# 1_Root.net
KiCad netlist of a schematic drawn in Altium Designer
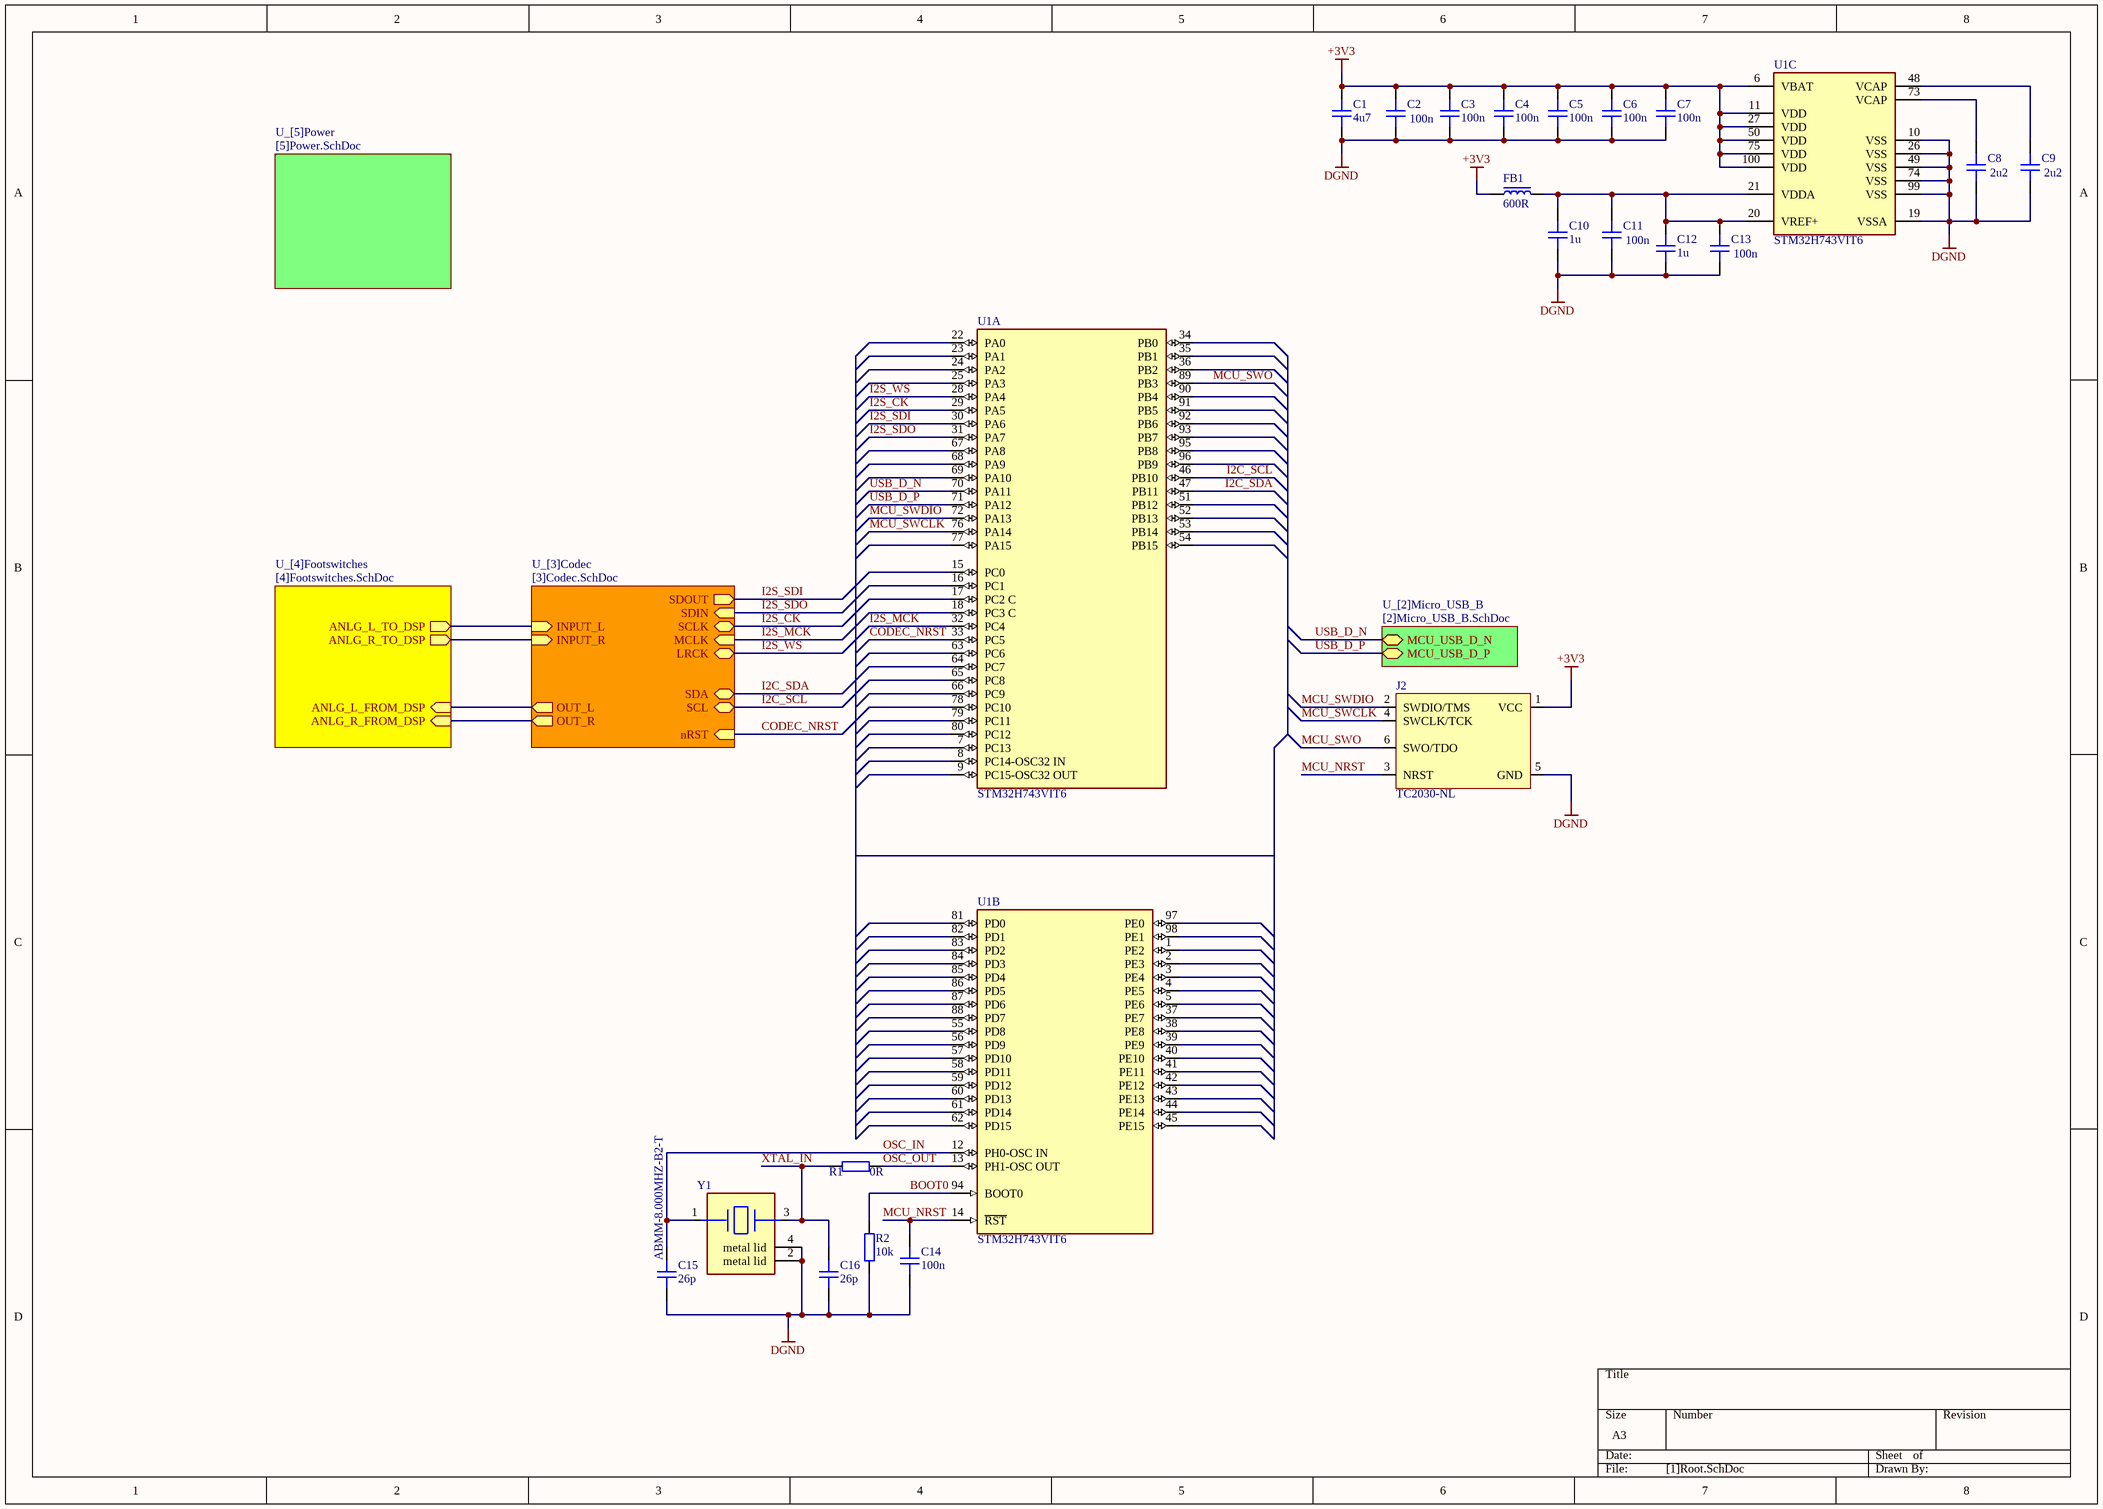
[diagram p0: [1]Root.SchDoc]

(export (version "E")
  (design (tool "Eeschema 10.0.6"))
  (components
    (comp (ref "C1")
      (value "4u7")
      (footprint "CAP_0603")
      (description "16V")
      (libsource (lib "Schematic-Lib-PhilsLab") (part "CAP_0603"))
    )
    (comp (ref "C2")
      (value "100n")
      (footprint "CAP_0402")
      (description "16V")
      (libsource (lib "Schematic-Lib-PhilsLab") (part "CAP_0402"))
    )
    (comp (ref "C3")
      (value "100n")
      (footprint "CAP_0402")
      (description "16V")
      (libsource (lib "Schematic-Lib-PhilsLab") (part "CAP_0402"))
    )
    (comp (ref "C4")
      (value "100n")
      (footprint "CAP_0402")
      (description "16V")
      (libsource (lib "Schematic-Lib-PhilsLab") (part "CAP_0402"))
    )
    (comp (ref "C5")
      (value "100n")
      (footprint "CAP_0402")
      (description "16V")
      (libsource (lib "Schematic-Lib-PhilsLab") (part "CAP_0402"))
    )
    (comp (ref "C6")
      (value "100n")
      (footprint "CAP_0402")
      (description "16V")
      (libsource (lib "Schematic-Lib-PhilsLab") (part "CAP_0402"))
    )
    (comp (ref "C7")
      (value "100n")
      (footprint "CAP_0402")
      (description "16V")
      (libsource (lib "Schematic-Lib-PhilsLab") (part "CAP_0402"))
    )
    (comp (ref "C8")
      (value "2u2")
      (footprint "CAP_0402")
      (description "16V")
      (libsource (lib "Schematic-Lib-PhilsLab") (part "CAP_0402"))
    )
    (comp (ref "C9")
      (value "2u2")
      (footprint "CAP_0402")
      (description "16V")
      (libsource (lib "Schematic-Lib-PhilsLab") (part "CAP_0402"))
    )
    (comp (ref "C10")
      (value "1u")
      (footprint "CAP_0603")
      (description "16V")
      (libsource (lib "Schematic-Lib-PhilsLab") (part "CAP_0603"))
    )
    (comp (ref "C11")
      (value "100n")
      (footprint "CAP_0402")
      (description "16V")
      (libsource (lib "Schematic-Lib-PhilsLab") (part "CAP_0402"))
    )
    (comp (ref "C12")
      (value "1u")
      (footprint "CAP_0603")
      (description "16V")
      (libsource (lib "Schematic-Lib-PhilsLab") (part "CAP_0603"))
    )
    (comp (ref "C13")
      (value "100n")
      (footprint "CAP_0402")
      (description "16V")
      (libsource (lib "Schematic-Lib-PhilsLab") (part "CAP_0402"))
    )
    (comp (ref "C14")
      (value "100n")
      (footprint "CAP_0402")
      (description "16V")
      (libsource (lib "Schematic-Lib-PhilsLab") (part "CAP_0402"))
    )
    (comp (ref "C15")
      (value "26p")
      (footprint "CAP_0402")
      (description "Capacitor SMD 0402")
      (libsource (lib "Schematic-Lib-PhilsLab") (part "CAP_0402"))
    )
    (comp (ref "C16")
      (value "26p")
      (footprint "CAP_0402")
      (description "Capacitor SMD 0402")
      (libsource (lib "Schematic-Lib-PhilsLab") (part "CAP_0402"))
    )
    (comp (ref "FB1")
      (value "600R")
      (footprint "FB_0805")
      (description "300mOhm DC, 600R @ 100MHz")
      (libsource (lib "Schematic-Lib-PhilsLab") (part "FB_0805"))
    )
    (comp (ref "J2")
      (value "TC2030-NL")
      (footprint "TC2030-NL-FP")
      (description "Tag-Connect No-Solder SWD Debug Connector (No Legs) DO NOT PLACE")
      (fields
        (field (name "MANUFACTURER") "Tag-Connect")
        (field (name "MANUFACTURER PART NUMBER") "TC2030-NL-FP")
      )
      (libsource (lib "Schematic-Lib-PhilsLab") (part "TC2030-NL"))
    )
    (comp (ref "R1")
      (value "0R")
      (footprint "RES_0402")
      (description "Resistor SMD 0402")
      (libsource (lib "Schematic-Lib-PhilsLab") (part "RES_0402"))
    )
    (comp (ref "R2")
      (value "10k")
      (footprint "RES_0402")
      (description "Resistor SMD 0402")
      (libsource (lib "Schematic-Lib-PhilsLab") (part "RES_0402"))
    )
    (comp (ref "U1")
      (value "STM32H743VIT6")
      (footprint "FP-LQFP100-1L-MFG")
      (description "IC MCU 32BIT 2MB FLASH 100LQFP")
      (fields
        (field (name "OCTOPART") "https://octopart.com/stm32h743vit6-stmicroelectronics-76372527")
        (field (name "MANUFACTURER") "STMicroelectronics")
      )
      (libsource (lib "Altium Content Vault") (part "01082ce2885d1d16a22823c45526fe6"))
    )
    (comp (ref "Y1")
      (value "ABMM-8.000MHZ-B2-T")
      (footprint "FP-ABMM-MFG")
      (description "CRYSTAL 8.0000MHZ 18PF SMD")
      (fields (field (name "TOLERANCE") "20ppm"))
      (libsource (lib "Altium Content Vault") (part "0c2a4651d804c61cb55e58ae8c0fb54"))
    )
  )
  (nets
    (net (code "1") (name "+3V3") (class "Default")
      (node (ref "C1") (pin "2") (pinfunction "2_2") (pintype "passive"))
      (node (ref "C2") (pin "2") (pinfunction "2_2") (pintype "passive"))
      (node (ref "C3") (pin "2") (pinfunction "2_2") (pintype "passive"))
      (node (ref "C4") (pin "2") (pinfunction "2_2") (pintype "passive"))
      (node (ref "C5") (pin "2") (pinfunction "2_2") (pintype "passive"))
      (node (ref "C6") (pin "2") (pinfunction "2_2") (pintype "passive"))
      (node (ref "C7") (pin "2") (pinfunction "2_2") (pintype "passive"))
      (node (ref "FB1") (pin "1") (pinfunction "1_1") (pintype "passive"))
      (node (ref "J2") (pin "1") (pinfunction "VCC_1") (pintype "passive"))
      (node (ref "U1") (pin "100") (pinfunction "VDD_100") (pintype "power_in"))
      (node (ref "U1") (pin "11") (pinfunction "VDD_11") (pintype "power_in"))
      (node (ref "U1") (pin "27") (pinfunction "VDD_27") (pintype "power_in"))
      (node (ref "U1") (pin "50") (pinfunction "VDD_50") (pintype "power_in"))
      (node (ref "U1") (pin "6") (pinfunction "VBAT_6") (pintype "power_in"))
      (node (ref "U1") (pin "75") (pinfunction "VDD_75") (pintype "power_in"))
    )
    (net (code "4") (name "/BOOT0") (class "Default")
      (node (ref "R2") (pin "2") (pinfunction "2_2") (pintype "passive"))
      (node (ref "U1") (pin "94") (pinfunction "BOOT0_94") (pintype "input"))
    )
    (net (code "5") (name "/CODEC_NRST") (class "Default")
      (node (ref "U1") (pin "33") (pinfunction "PC5_33") (pintype "bidirectional"))
    )
    (net (code "6") (name "/I2C_SCL") (class "Default")
      (node (ref "U1") (pin "46") (pinfunction "PB10_46") (pintype "bidirectional"))
    )
    (net (code "7") (name "/I2C_SDA") (class "Default")
      (node (ref "U1") (pin "47") (pinfunction "PB11_47") (pintype "bidirectional"))
    )
    (net (code "8") (name "/I2S_CK") (class "Default")
      (node (ref "U1") (pin "29") (pinfunction "PA5_29") (pintype "bidirectional"))
    )
    (net (code "9") (name "/I2S_MCK") (class "Default")
      (node (ref "U1") (pin "32") (pinfunction "PC4_32") (pintype "bidirectional"))
    )
    (net (code "10") (name "/I2S_SDI") (class "Default")
      (node (ref "U1") (pin "30") (pinfunction "PA6_30") (pintype "bidirectional"))
    )
    (net (code "11") (name "/I2S_SDO") (class "Default")
      (node (ref "U1") (pin "31") (pinfunction "PA7_31") (pintype "bidirectional"))
    )
    (net (code "12") (name "/I2S_WS") (class "Default")
      (node (ref "U1") (pin "28") (pinfunction "PA4_28") (pintype "bidirectional"))
    )
    (net (code "13") (name "/MCU_NRST") (class "Default")
      (node (ref "C14") (pin "2") (pinfunction "2_2") (pintype "passive"))
      (node (ref "J2") (pin "3") (pinfunction "NRST_3") (pintype "passive"))
      (node (ref "U1") (pin "14") (pinfunction "~{RST}_14") (pintype "input"))
    )
    (net (code "14") (name "/MCU_SWCLK") (class "Default")
      (node (ref "J2") (pin "4") (pinfunction "SWCLK/TCK_4") (pintype "passive"))
      (node (ref "U1") (pin "76") (pinfunction "PA14_76") (pintype "bidirectional"))
    )
    (net (code "15") (name "/MCU_SWDIO") (class "Default")
      (node (ref "J2") (pin "2") (pinfunction "SWDIO/TMS_2") (pintype "passive"))
      (node (ref "U1") (pin "72") (pinfunction "PA13_72") (pintype "bidirectional"))
    )
    (net (code "16") (name "/MCU_SWO") (class "Default")
      (node (ref "J2") (pin "6") (pinfunction "SWO/TDO_6") (pintype "passive"))
      (node (ref "U1") (pin "89") (pinfunction "PB3_89") (pintype "bidirectional"))
    )
    (net (code "17") (name "/OSC_IN") (class "Default")
      (node (ref "C15") (pin "2") (pinfunction "2_2") (pintype "passive"))
      (node (ref "U1") (pin "12") (pinfunction "PH0-OSC_IN_12") (pintype "bidirectional"))
      (node (ref "Y1") (pin "1") (pinfunction "1_1") (pintype "passive"))
    )
    (net (code "18") (name "/OSC_OUT") (class "Default")
      (node (ref "R1") (pin "2") (pinfunction "2_2") (pintype "passive"))
      (node (ref "U1") (pin "13") (pinfunction "PH1-OSC_OUT_13") (pintype "bidirectional"))
    )
    (net (code "21") (name "/USB_D_N") (class "Default")
      (node (ref "U1") (pin "70") (pinfunction "PA11_70") (pintype "bidirectional"))
    )
    (net (code "22") (name "/USB_D_P") (class "Default")
      (node (ref "U1") (pin "71") (pinfunction "PA12_71") (pintype "bidirectional"))
    )
    (net (code "23") (name "/XTAL_IN") (class "Default")
      (node (ref "C16") (pin "2") (pinfunction "2_2") (pintype "passive"))
      (node (ref "R1") (pin "1") (pinfunction "1_1") (pintype "passive"))
      (node (ref "Y1") (pin "3") (pinfunction "3_3") (pintype "passive"))
    )
    (net (code "24") (name "DGND") (class "Default")
      (node (ref "C1") (pin "1") (pinfunction "1_1") (pintype "passive"))
      (node (ref "C10") (pin "1") (pinfunction "1_1") (pintype "passive"))
      (node (ref "C11") (pin "1") (pinfunction "1_1") (pintype "passive"))
      (node (ref "C12") (pin "1") (pinfunction "1_1") (pintype "passive"))
      (node (ref "C13") (pin "1") (pinfunction "1_1") (pintype "passive"))
      (node (ref "C14") (pin "1") (pinfunction "1_1") (pintype "passive"))
      (node (ref "C15") (pin "1") (pinfunction "1_1") (pintype "passive"))
      (node (ref "C16") (pin "1") (pinfunction "1_1") (pintype "passive"))
      (node (ref "C2") (pin "1") (pinfunction "1_1") (pintype "passive"))
      (node (ref "C3") (pin "1") (pinfunction "1_1") (pintype "passive"))
      (node (ref "C4") (pin "1") (pinfunction "1_1") (pintype "passive"))
      (node (ref "C5") (pin "1") (pinfunction "1_1") (pintype "passive"))
      (node (ref "C6") (pin "1") (pinfunction "1_1") (pintype "passive"))
      (node (ref "C7") (pin "1") (pinfunction "1_1") (pintype "passive"))
      (node (ref "C8") (pin "1") (pinfunction "1_1") (pintype "passive"))
      (node (ref "C9") (pin "1") (pinfunction "1_1") (pintype "passive"))
      (node (ref "J2") (pin "5") (pinfunction "GND_5") (pintype "passive"))
      (node (ref "R2") (pin "1") (pinfunction "1_1") (pintype "passive"))
      (node (ref "U1") (pin "10") (pinfunction "VSS_10") (pintype "power_in"))
      (node (ref "U1") (pin "19") (pinfunction "VSSA_19") (pintype "power_in"))
      (node (ref "U1") (pin "26") (pinfunction "VSS_26") (pintype "power_in"))
      (node (ref "U1") (pin "49") (pinfunction "VSS_49") (pintype "power_in"))
      (node (ref "U1") (pin "74") (pinfunction "VSS_74") (pintype "power_in"))
      (node (ref "U1") (pin "99") (pinfunction "VSS_99") (pintype "power_in"))
      (node (ref "Y1") (pin "2") (pinfunction "metal_lid_2") (pintype "passive"))
      (node (ref "Y1") (pin "4") (pinfunction "metal_lid_4") (pintype "passive"))
    )
    (net (code "25") (name "Net-(C8-Pad2)") (class "Default")
      (node (ref "C8") (pin "2") (pinfunction "2_2") (pintype "passive"))
      (node (ref "U1") (pin "73") (pinfunction "VCAP_73") (pintype "passive"))
    )
    (net (code "26") (name "Net-(C9-Pad2)") (class "Default")
      (node (ref "C9") (pin "2") (pinfunction "2_2") (pintype "passive"))
      (node (ref "U1") (pin "48") (pinfunction "VCAP_48") (pintype "passive"))
    )
    (net (code "27") (name "Net-(U1C-VDDA)") (class "Default")
      (node (ref "C10") (pin "2") (pinfunction "2_2") (pintype "passive"))
      (node (ref "C11") (pin "2") (pinfunction "2_2") (pintype "passive"))
      (node (ref "C12") (pin "2") (pinfunction "2_2") (pintype "passive"))
      (node (ref "C13") (pin "2") (pinfunction "2_2") (pintype "passive"))
      (node (ref "FB1") (pin "2") (pinfunction "2_2") (pintype "passive"))
      (node (ref "U1") (pin "20") (pinfunction "VREF+_20") (pintype "power_in"))
      (node (ref "U1") (pin "21") (pinfunction "VDDA_21") (pintype "power_in"))
    )
    (net (code "28") (name "unconnected-(U1A-PA0-Pad22)") (class "Default")
      (node (ref "U1") (pin "22") (pinfunction "PA0_22") (pintype "bidirectional"))
    )
    (net (code "29") (name "unconnected-(U1A-PA1-Pad23)") (class "Default")
      (node (ref "U1") (pin "23") (pinfunction "PA1_23") (pintype "bidirectional"))
    )
    (net (code "30") (name "unconnected-(U1A-PA2-Pad24)") (class "Default")
      (node (ref "U1") (pin "24") (pinfunction "PA2_24") (pintype "bidirectional"))
    )
    (net (code "31") (name "unconnected-(U1A-PA3-Pad25)") (class "Default")
      (node (ref "U1") (pin "25") (pinfunction "PA3_25") (pintype "bidirectional"))
    )
    (net (code "32") (name "unconnected-(U1A-PA8-Pad67)") (class "Default")
      (node (ref "U1") (pin "67") (pinfunction "PA8_67") (pintype "bidirectional"))
    )
    (net (code "33") (name "unconnected-(U1A-PA9-Pad68)") (class "Default")
      (node (ref "U1") (pin "68") (pinfunction "PA9_68") (pintype "bidirectional"))
    )
    (net (code "34") (name "unconnected-(U1A-PA10-Pad69)") (class "Default")
      (node (ref "U1") (pin "69") (pinfunction "PA10_69") (pintype "bidirectional"))
    )
    (net (code "35") (name "unconnected-(U1A-PA15-Pad77)") (class "Default")
      (node (ref "U1") (pin "77") (pinfunction "PA15_77") (pintype "bidirectional"))
    )
    (net (code "36") (name "unconnected-(U1A-PB0-Pad34)") (class "Default")
      (node (ref "U1") (pin "34") (pinfunction "PB0_34") (pintype "bidirectional"))
    )
    (net (code "37") (name "unconnected-(U1A-PB1-Pad35)") (class "Default")
      (node (ref "U1") (pin "35") (pinfunction "PB1_35") (pintype "bidirectional"))
    )
    (net (code "38") (name "unconnected-(U1A-PB2-Pad36)") (class "Default")
      (node (ref "U1") (pin "36") (pinfunction "PB2_36") (pintype "bidirectional"))
    )
    (net (code "39") (name "unconnected-(U1A-PB4-Pad90)") (class "Default")
      (node (ref "U1") (pin "90") (pinfunction "PB4_90") (pintype "bidirectional"))
    )
    (net (code "40") (name "unconnected-(U1A-PB5-Pad91)") (class "Default")
      (node (ref "U1") (pin "91") (pinfunction "PB5_91") (pintype "bidirectional"))
    )
    (net (code "41") (name "unconnected-(U1A-PB6-Pad92)") (class "Default")
      (node (ref "U1") (pin "92") (pinfunction "PB6_92") (pintype "bidirectional"))
    )
    (net (code "42") (name "unconnected-(U1A-PB7-Pad93)") (class "Default")
      (node (ref "U1") (pin "93") (pinfunction "PB7_93") (pintype "bidirectional"))
    )
    (net (code "43") (name "unconnected-(U1A-PB8-Pad95)") (class "Default")
      (node (ref "U1") (pin "95") (pinfunction "PB8_95") (pintype "bidirectional"))
    )
    (net (code "44") (name "unconnected-(U1A-PB9-Pad96)") (class "Default")
      (node (ref "U1") (pin "96") (pinfunction "PB9_96") (pintype "bidirectional"))
    )
    (net (code "45") (name "unconnected-(U1A-PB12-Pad51)") (class "Default")
      (node (ref "U1") (pin "51") (pinfunction "PB12_51") (pintype "bidirectional"))
    )
    (net (code "46") (name "unconnected-(U1A-PB13-Pad52)") (class "Default")
      (node (ref "U1") (pin "52") (pinfunction "PB13_52") (pintype "bidirectional"))
    )
    (net (code "47") (name "unconnected-(U1A-PB14-Pad53)") (class "Default")
      (node (ref "U1") (pin "53") (pinfunction "PB14_53") (pintype "bidirectional"))
    )
    (net (code "48") (name "unconnected-(U1A-PB15-Pad54)") (class "Default")
      (node (ref "U1") (pin "54") (pinfunction "PB15_54") (pintype "bidirectional"))
    )
    (net (code "49") (name "unconnected-(U1A-PC0-Pad15)") (class "Default")
      (node (ref "U1") (pin "15") (pinfunction "PC0_15") (pintype "bidirectional"))
    )
    (net (code "50") (name "unconnected-(U1A-PC1-Pad16)") (class "Default")
      (node (ref "U1") (pin "16") (pinfunction "PC1_16") (pintype "bidirectional"))
    )
    (net (code "51") (name "unconnected-(U1A-PC2_C-Pad17)") (class "Default")
      (node (ref "U1") (pin "17") (pinfunction "PC2_C_17") (pintype "bidirectional"))
    )
    (net (code "52") (name "unconnected-(U1A-PC3_C-Pad18)") (class "Default")
      (node (ref "U1") (pin "18") (pinfunction "PC3_C_18") (pintype "bidirectional"))
    )
    (net (code "53") (name "unconnected-(U1A-PC6-Pad63)") (class "Default")
      (node (ref "U1") (pin "63") (pinfunction "PC6_63") (pintype "bidirectional"))
    )
    (net (code "54") (name "unconnected-(U1A-PC7-Pad64)") (class "Default")
      (node (ref "U1") (pin "64") (pinfunction "PC7_64") (pintype "bidirectional"))
    )
    (net (code "55") (name "unconnected-(U1A-PC8-Pad65)") (class "Default")
      (node (ref "U1") (pin "65") (pinfunction "PC8_65") (pintype "bidirectional"))
    )
    (net (code "56") (name "unconnected-(U1A-PC9-Pad66)") (class "Default")
      (node (ref "U1") (pin "66") (pinfunction "PC9_66") (pintype "bidirectional"))
    )
    (net (code "57") (name "unconnected-(U1A-PC10-Pad78)") (class "Default")
      (node (ref "U1") (pin "78") (pinfunction "PC10_78") (pintype "bidirectional"))
    )
    (net (code "58") (name "unconnected-(U1A-PC11-Pad79)") (class "Default")
      (node (ref "U1") (pin "79") (pinfunction "PC11_79") (pintype "bidirectional"))
    )
    (net (code "59") (name "unconnected-(U1A-PC12-Pad80)") (class "Default")
      (node (ref "U1") (pin "80") (pinfunction "PC12_80") (pintype "bidirectional"))
    )
    (net (code "60") (name "unconnected-(U1A-PC13-Pad7)") (class "Default")
      (node (ref "U1") (pin "7") (pinfunction "PC13_7") (pintype "bidirectional"))
    )
    (net (code "61") (name "unconnected-(U1A-PC14-OSC32_IN-Pad8)") (class "Default")
      (node (ref "U1") (pin "8") (pinfunction "PC14-OSC32_IN_8") (pintype "bidirectional"))
    )
    (net (code "62") (name "unconnected-(U1A-PC15-OSC32_OUT-Pad9)") (class "Default")
      (node (ref "U1") (pin "9") (pinfunction "PC15-OSC32_OUT_9") (pintype "bidirectional"))
    )
    (net (code "63") (name "unconnected-(U1B-PD0-Pad81)") (class "Default")
      (node (ref "U1") (pin "81") (pinfunction "PD0_81") (pintype "bidirectional"))
    )
    (net (code "64") (name "unconnected-(U1B-PD1-Pad82)") (class "Default")
      (node (ref "U1") (pin "82") (pinfunction "PD1_82") (pintype "bidirectional"))
    )
    (net (code "65") (name "unconnected-(U1B-PD2-Pad83)") (class "Default")
      (node (ref "U1") (pin "83") (pinfunction "PD2_83") (pintype "bidirectional"))
    )
    (net (code "66") (name "unconnected-(U1B-PD3-Pad84)") (class "Default")
      (node (ref "U1") (pin "84") (pinfunction "PD3_84") (pintype "bidirectional"))
    )
    (net (code "67") (name "unconnected-(U1B-PD4-Pad85)") (class "Default")
      (node (ref "U1") (pin "85") (pinfunction "PD4_85") (pintype "bidirectional"))
    )
    (net (code "68") (name "unconnected-(U1B-PD5-Pad86)") (class "Default")
      (node (ref "U1") (pin "86") (pinfunction "PD5_86") (pintype "bidirectional"))
    )
    (net (code "69") (name "unconnected-(U1B-PD6-Pad87)") (class "Default")
      (node (ref "U1") (pin "87") (pinfunction "PD6_87") (pintype "bidirectional"))
    )
    (net (code "70") (name "unconnected-(U1B-PD7-Pad88)") (class "Default")
      (node (ref "U1") (pin "88") (pinfunction "PD7_88") (pintype "bidirectional"))
    )
    (net (code "71") (name "unconnected-(U1B-PD8-Pad55)") (class "Default")
      (node (ref "U1") (pin "55") (pinfunction "PD8_55") (pintype "bidirectional"))
    )
    (net (code "72") (name "unconnected-(U1B-PD9-Pad56)") (class "Default")
      (node (ref "U1") (pin "56") (pinfunction "PD9_56") (pintype "bidirectional"))
    )
    (net (code "73") (name "unconnected-(U1B-PD10-Pad57)") (class "Default")
      (node (ref "U1") (pin "57") (pinfunction "PD10_57") (pintype "bidirectional"))
    )
    (net (code "74") (name "unconnected-(U1B-PD11-Pad58)") (class "Default")
      (node (ref "U1") (pin "58") (pinfunction "PD11_58") (pintype "bidirectional"))
    )
    (net (code "75") (name "unconnected-(U1B-PD12-Pad59)") (class "Default")
      (node (ref "U1") (pin "59") (pinfunction "PD12_59") (pintype "bidirectional"))
    )
    (net (code "76") (name "unconnected-(U1B-PD13-Pad60)") (class "Default")
      (node (ref "U1") (pin "60") (pinfunction "PD13_60") (pintype "bidirectional"))
    )
    (net (code "77") (name "unconnected-(U1B-PD14-Pad61)") (class "Default")
      (node (ref "U1") (pin "61") (pinfunction "PD14_61") (pintype "bidirectional"))
    )
    (net (code "78") (name "unconnected-(U1B-PD15-Pad62)") (class "Default")
      (node (ref "U1") (pin "62") (pinfunction "PD15_62") (pintype "bidirectional"))
    )
    (net (code "79") (name "unconnected-(U1B-PE0-Pad97)") (class "Default")
      (node (ref "U1") (pin "97") (pinfunction "PE0_97") (pintype "bidirectional"))
    )
    (net (code "80") (name "unconnected-(U1B-PE1-Pad98)") (class "Default")
      (node (ref "U1") (pin "98") (pinfunction "PE1_98") (pintype "bidirectional"))
    )
    (net (code "81") (name "unconnected-(U1B-PE2-Pad1)") (class "Default")
      (node (ref "U1") (pin "1") (pinfunction "PE2_1") (pintype "bidirectional"))
    )
    (net (code "82") (name "unconnected-(U1B-PE3-Pad2)") (class "Default")
      (node (ref "U1") (pin "2") (pinfunction "PE3_2") (pintype "bidirectional"))
    )
    (net (code "83") (name "unconnected-(U1B-PE4-Pad3)") (class "Default")
      (node (ref "U1") (pin "3") (pinfunction "PE4_3") (pintype "bidirectional"))
    )
    (net (code "84") (name "unconnected-(U1B-PE5-Pad4)") (class "Default")
      (node (ref "U1") (pin "4") (pinfunction "PE5_4") (pintype "bidirectional"))
    )
    (net (code "85") (name "unconnected-(U1B-PE6-Pad5)") (class "Default")
      (node (ref "U1") (pin "5") (pinfunction "PE6_5") (pintype "bidirectional"))
    )
    (net (code "86") (name "unconnected-(U1B-PE7-Pad37)") (class "Default")
      (node (ref "U1") (pin "37") (pinfunction "PE7_37") (pintype "bidirectional"))
    )
    (net (code "87") (name "unconnected-(U1B-PE8-Pad38)") (class "Default")
      (node (ref "U1") (pin "38") (pinfunction "PE8_38") (pintype "bidirectional"))
    )
    (net (code "88") (name "unconnected-(U1B-PE9-Pad39)") (class "Default")
      (node (ref "U1") (pin "39") (pinfunction "PE9_39") (pintype "bidirectional"))
    )
    (net (code "89") (name "unconnected-(U1B-PE10-Pad40)") (class "Default")
      (node (ref "U1") (pin "40") (pinfunction "PE10_40") (pintype "bidirectional"))
    )
    (net (code "90") (name "unconnected-(U1B-PE11-Pad41)") (class "Default")
      (node (ref "U1") (pin "41") (pinfunction "PE11_41") (pintype "bidirectional"))
    )
    (net (code "91") (name "unconnected-(U1B-PE12-Pad42)") (class "Default")
      (node (ref "U1") (pin "42") (pinfunction "PE12_42") (pintype "bidirectional"))
    )
    (net (code "92") (name "unconnected-(U1B-PE13-Pad43)") (class "Default")
      (node (ref "U1") (pin "43") (pinfunction "PE13_43") (pintype "bidirectional"))
    )
    (net (code "93") (name "unconnected-(U1B-PE14-Pad44)") (class "Default")
      (node (ref "U1") (pin "44") (pinfunction "PE14_44") (pintype "bidirectional"))
    )
    (net (code "94") (name "unconnected-(U1B-PE15-Pad45)") (class "Default")
      (node (ref "U1") (pin "45") (pinfunction "PE15_45") (pintype "bidirectional"))
    )
  )
)
